# CV060_POWER.net
KiCad netlist of a schematic drawn in Altium Designer
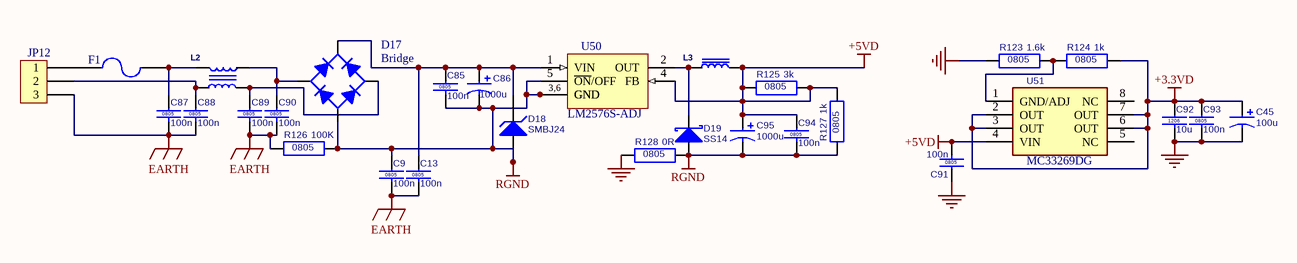
[diagram p0: CV060_POWER.SchDoc]

(export (version "E")
  (design (tool "Eeschema 10.0.6"))
  (components
    (comp (ref "C9")
      (value "100n")
      (footprint "RC0805")
      (description "Chip capacitor, 20p")
      (fields
        (field (name "VOLTAGE") "50V")
        (field (name "MANUFACTURER") "KEMET, YAGEO")
        (field (name "CASE") "0805")
        (field (name "PUBLISHER") "ppavlov")
      )
      (libsource (lib "Aldiva_Altium_Library") (part "Capacitor_nonpolar_case"))
    )
    (comp (ref "C13")
      (value "100n")
      (footprint "RC0805")
      (description "Chip capacitor, 20p")
      (fields
        (field (name "VOLTAGE") "50V")
        (field (name "MANUFACTURER") "KEMET, YAGEO")
        (field (name "CASE") "0805")
        (field (name "PUBLISHER") "ppavlov")
      )
      (libsource (lib "Aldiva_Altium_Library") (part "Capacitor_nonpolar_case"))
    )
    (comp (ref "C45")
      (value "100u")
      (footprint "CEH12.5D5P2.5")
      (description "Electrolytic capacitor")
      (fields
        (field (name "PART NUMBER") "CEH12.5D5P2.5M-16V-100U")
        (field (name "VOLTAGE") "16V")
        (field (name "PUBLISHER") "ppavlov")
      )
      (libsource (lib "Aldiva_Altium_Library") (part "Capacitor_polar"))
    )
    (comp (ref "C85")
      (value "100n")
      (footprint "RC0805")
      (description "Chip capacitor, 20p")
      (fields
        (field (name "VOLTAGE") "50V")
        (field (name "MANUFACTURER") "KEMET, YAGEO")
        (field (name "CASE") "0805")
        (field (name "PUBLISHER") "ppavlov")
      )
      (libsource (lib "Aldiva_Altium_Library") (part "Capacitor_nonpolar_case"))
    )
    (comp (ref "C86")
      (value "1000u")
      (footprint "CEH25D18P7.5")
      (description "Electrolytic capacitor")
      (fields
        (field (name "PART NUMBER") "CEH25D12.5P5.0M-50V-1000U")
        (field (name "VOLTAGE") "50V")
        (field (name "PUBLISHER") "ppavlov")
      )
      (libsource (lib "Aldiva_Altium_Library") (part "Capacitor_polar"))
    )
    (comp (ref "C87")
      (value "100n")
      (footprint "RC0805")
      (description "Chip capacitor, 20p")
      (fields
        (field (name "VOLTAGE") "50V")
        (field (name "MANUFACTURER") "KEMET, YAGEO")
        (field (name "CASE") "0805")
        (field (name "PUBLISHER") "ppavlov")
      )
      (libsource (lib "Aldiva_Altium_Library") (part "Capacitor_nonpolar_case"))
    )
    (comp (ref "C88")
      (value "100n")
      (footprint "RC0805")
      (description "Chip capacitor, 20p")
      (fields
        (field (name "VOLTAGE") "50V")
        (field (name "MANUFACTURER") "KEMET, YAGEO")
        (field (name "CASE") "0805")
        (field (name "PUBLISHER") "ppavlov")
      )
      (libsource (lib "Aldiva_Altium_Library") (part "Capacitor_nonpolar_case"))
    )
    (comp (ref "C89")
      (value "100n")
      (footprint "RC0805")
      (description "Chip capacitor, 20p")
      (fields
        (field (name "VOLTAGE") "50V")
        (field (name "MANUFACTURER") "KEMET, YAGEO")
        (field (name "CASE") "0805")
        (field (name "PUBLISHER") "ppavlov")
      )
      (libsource (lib "Aldiva_Altium_Library") (part "Capacitor_nonpolar_case"))
    )
    (comp (ref "C90")
      (value "100n")
      (footprint "RC0805")
      (description "Chip capacitor, 20p")
      (fields
        (field (name "VOLTAGE") "50V")
        (field (name "MANUFACTURER") "KEMET, YAGEO")
        (field (name "CASE") "0805")
        (field (name "PUBLISHER") "ppavlov")
      )
      (libsource (lib "Aldiva_Altium_Library") (part "Capacitor_nonpolar_case"))
    )
    (comp (ref "C91")
      (value "100n")
      (footprint "RC0805")
      (description "Chip capacitor, 20p")
      (fields
        (field (name "VOLTAGE") "50V")
        (field (name "MANUFACTURER") "KEMET, YAGEO")
        (field (name "CASE") "0805")
        (field (name "PUBLISHER") "ppavlov")
      )
      (libsource (lib "Aldiva_Altium_Library") (part "Capacitor_nonpolar_case"))
    )
    (comp (ref "C92")
      (value "10u")
      (footprint "RC1206")
      (description "Chip capacitor, 20p")
      (fields
        (field (name "VOLTAGE") "10V")
        (field (name "MANUFACTURER") "AVX")
        (field (name "CASE") "1206")
        (field (name "PUBLISHER") "tkondratyuk")
      )
      (libsource (lib "Aldiva_Altium_Library") (part "Capacitor_nonpolar_case"))
    )
    (comp (ref "C93")
      (value "100n")
      (footprint "RC0805")
      (description "Chip capacitor, 20p")
      (fields
        (field (name "VOLTAGE") "50V")
        (field (name "MANUFACTURER") "KEMET, YAGEO")
        (field (name "CASE") "0805")
        (field (name "PUBLISHER") "ppavlov")
      )
      (libsource (lib "Aldiva_Altium_Library") (part "Capacitor_nonpolar_case"))
    )
    (comp (ref "C94")
      (value "100n")
      (footprint "RC0805")
      (description "Chip capacitor, 20p")
      (fields
        (field (name "VOLTAGE") "50V")
        (field (name "MANUFACTURER") "KEMET, YAGEO")
        (field (name "CASE") "0805")
        (field (name "PUBLISHER") "ppavlov")
      )
      (libsource (lib "Aldiva_Altium_Library") (part "Capacitor_nonpolar_case"))
    )
    (comp (ref "C95")
      (value "1000u")
      (footprint "CEH12.5D10P5.0")
      (description "Electrolytic capacitor")
      (fields
        (field (name "PART NUMBER") "CEH25D12.5P5.0M-35V-1000U")
        (field (name "VOLTAGE") "35V")
        (field (name "PUBLISHER") "ppavlov")
      )
      (libsource (lib "Aldiva_Altium_Library") (part "Capacitor_polar"))
    )
    (comp (ref "D17")
      (value "Bridge")
      (footprint "KBPM")
      (description "Bridge 2A 600V")
      (fields
        (field (name "PART NUMBER") "2KBP06M")
        (field (name "VOLTAGE") "600V")
        (field (name "PUBLISHER") "ppavlov")
      )
      (libsource (lib "Aldiva_Altium_Library") (part "Bridge"))
    )
    (comp (ref "D18")
      (value "Zenner_diode")
      (footprint "SMB")
      (description "Transient Voltage Suppressor")
      (fields
        (field (name "PART NUMBER") "SMBJ24")
        (field (name "VOLTAGE") "24V")
        (field (name "MANUFACTURER") "Fairchild")
        (field (name "PUBLISHER") "tkondratyuk")
      )
      (libsource (lib "Aldiva_Altium_Library") (part "Zenner_diode"))
    )
    (comp (ref "D19")
      (value "Schottky_diode")
      (footprint "SMA")
      (description "Surface Mount Schottky Barrier Rectifier")
      (fields
        (field (name "PART NUMBER") "SS14")
        (field (name "VOLTAGE") "40V")
        (field (name "MANUFACTURER") "Fairchild, Vishay")
        (field (name "PUBLISHER") "tkondratyuk")
      )
      (libsource (lib "Aldiva_Altium_Library") (part "Schottky_diode"))
    )
    (comp (ref "F1")
      (value "RXEF135")
      (footprint "POLYSW_RXEF135")
      (description "Polyswitch RXEF135 fuse")
      (fields
        (field (name "VOLTAGE") "72V")
        (field (name "MANUFACTURER") "Polyswitch")
        (field (name "PUBLISHER") "ppavlov")
      )
      (libsource (lib "Aldiva_Altium_Library") (part "RXEF135"))
    )
    (comp (ref "JP12")
      (value "Header 3pins")
      (footprint "PHENIX_5MM _3p3D")
      (description "5.08mm angled 3pins receptabe")
      (fields (field (name "PART NUMBER") "2EDGR-5.0-03P-14") (field (name "PUBLISHER") "ppavlov"))
      (libsource (lib "Aldiva_Altium_Library") (part "Header 3pins"))
    )
    (comp (ref "L2")
      (value "linear_filter1")
      (footprint "UU157-01")
      (description "Linear filter")
      (fields
        (field (name "PART NUMBER") "UU157-01")
        (field (name "TOLERANCE") "20%")
        (field (name "AUTHOR") "PPavlov")
        (field (name "PUBLISHER") "ppavlov")
      )
      (libsource (lib "Aldiva_Altium_Library") (part "linear_filter1"))
    )
    (comp (ref "L3")
      (value "INDUCTOR2")
      (footprint "IH12.5D10P5.0")
      (description "Through hole Power Inductor")
      (fields
        (field (name "PART NUMBER") "RB0914-151KLA")
        (field (name "TOLERANCE") "20%")
        (field (name "AUTHOR") "PPavlov")
        (field (name "PUBLISHER") "ppavlov")
      )
      (libsource (lib "Aldiva_Altium_Library") (part "INDUCTOR2"))
    )
    (comp (ref "R123")
      (value "1.6k")
      (footprint "RC0805")
      (description "Chip resistor")
      (fields
        (field (name "CASE") "0805")
        (field (name "PART NUMBER") "RC0805F-1K60")
        (field (name "VOLTAGE") "200V")
        (field (name "PUBLISHER") "ppavlov")
      )
      (libsource (lib "Aldiva_Altium_Library") (part "Resistor"))
    )
    (comp (ref "R124")
      (value "1k")
      (footprint "RC0805")
      (description "Chip resistor")
      (fields
        (field (name "CASE") "0805")
        (field (name "PART NUMBER") "RC0805F-1K00")
        (field (name "VOLTAGE") "200V")
        (field (name "PUBLISHER") "ppavlov")
      )
      (libsource (lib "Aldiva_Altium_Library") (part "Resistor"))
    )
    (comp (ref "R125")
      (value "3k")
      (footprint "RC0805")
      (description "Chip resistor")
      (fields
        (field (name "CASE") "0805")
        (field (name "PART NUMBER") "RC0805F-3K00")
        (field (name "VOLTAGE") "200V")
        (field (name "PUBLISHER") "ppavlov")
      )
      (libsource (lib "Aldiva_Altium_Library") (part "Resistor"))
    )
    (comp (ref "R126")
      (value "100K")
      (footprint "RC0805")
      (description "Chip resistor")
      (fields
        (field (name "CASE") "0805")
        (field (name "PART NUMBER") "RC0805F-100K")
        (field (name "VOLTAGE") "200V")
        (field (name "PUBLISHER") "ppavlov")
      )
      (libsource (lib "Aldiva_Altium_Library") (part "Resistor"))
    )
    (comp (ref "R127")
      (value "1k")
      (footprint "RC0805")
      (description "Chip resistor")
      (fields
        (field (name "CASE") "0805")
        (field (name "PART NUMBER") "RC0805F-1K00")
        (field (name "VOLTAGE") "200V")
        (field (name "PUBLISHER") "ppavlov")
      )
      (libsource (lib "Aldiva_Altium_Library") (part "Resistor"))
    )
    (comp (ref "R128")
      (value "0R")
      (footprint "RC0805")
      (description "Chip resistor")
      (fields
        (field (name "CASE") "0805")
        (field (name "PART NUMBER") "RC0805F-000R")
        (field (name "VOLTAGE") "200V")
        (field (name "PUBLISHER") "ppavlov")
      )
      (libsource (lib "Aldiva_Altium_Library") (part "Resistor"))
    )
    (comp (ref "U50")
      (value "LM2576S-ADJ")
      (footprint "TO-263")
      (description "3A Step-Down Voltage Regulator")
      (fields (field (name "MANUFACTURER") "National semiconductor") (field (name "PUBLISHER") "ppavlov"))
      (libsource (lib "Aldiva_Altium_Library") (part "LM2576S-ADJ"))
    )
    (comp (ref "U51")
      (value "MC33269DG")
      (footprint "SO-8")
      (description "LDO 800ma ADJ")
      (fields
        (field (name "PART NUMBER") "MC33269DG")
        (field (name "MANUFACTURER") "ON Semiconductor")
        (field (name "PUBLISHER") "ppavlov")
      )
      (libsource (lib "Aldiva_Altium_Library") (part "MC33269D"))
    )
  )
  (nets
    (net (code "1") (name "+3.3VD") (class "Default")
      (node (ref "C45") (pin "1") (pinfunction "1_1") (pintype "passive"))
      (node (ref "C92") (pin "1") (pinfunction "1_1") (pintype "passive"))
      (node (ref "C93") (pin "1") (pinfunction "1_1") (pintype "passive"))
      (node (ref "R124") (pin "2") (pinfunction "2_2") (pintype "passive"))
      (node (ref "U51") (pin "2") (pinfunction "OUT_2") (pintype "passive"))
      (node (ref "U51") (pin "3") (pinfunction "OUT_3") (pintype "passive"))
      (node (ref "U51") (pin "6") (pinfunction "OUT_6") (pintype "passive"))
      (node (ref "U51") (pin "7") (pinfunction "OUT_7") (pintype "passive"))
    )
    (net (code "2") (name "+5VD") (class "Default")
      (node (ref "C91") (pin "2") (pinfunction "2_2") (pintype "passive"))
      (node (ref "C94") (pin "1") (pinfunction "1_1") (pintype "passive"))
      (node (ref "C95") (pin "1") (pinfunction "1_1") (pintype "passive"))
      (node (ref "L3") (pin "2") (pinfunction "2_2") (pintype "passive"))
      (node (ref "R125") (pin "1") (pinfunction "1_1") (pintype "passive"))
      (node (ref "R125") (pin "2") (pinfunction "2_2") (pintype "passive"))
      (node (ref "R127") (pin "2") (pinfunction "2_2") (pintype "passive"))
      (node (ref "U50") (pin "4") (pinfunction "FB_4") (pintype "input"))
      (node (ref "U51") (pin "4") (pinfunction "VIN_4") (pintype "passive"))
    )
    (net (code "3") (name "DGND") (class "Default")
      (node (ref "C45") (pin "2") (pinfunction "2_2") (pintype "passive"))
      (node (ref "C91") (pin "1") (pinfunction "1_1") (pintype "passive"))
      (node (ref "C92") (pin "2") (pinfunction "2_2") (pintype "passive"))
      (node (ref "C93") (pin "2") (pinfunction "2_2") (pintype "passive"))
      (node (ref "R123") (pin "1") (pinfunction "1_1") (pintype "passive"))
      (node (ref "R128") (pin "1") (pinfunction "1_1") (pintype "passive"))
    )
    (net (code "4") (name "EARTH") (class "Default")
      (node (ref "C13") (pin "2") (pinfunction "2_2") (pintype "passive"))
      (node (ref "C87") (pin "2") (pinfunction "2_2") (pintype "passive"))
      (node (ref "C88") (pin "2") (pinfunction "2_2") (pintype "passive"))
      (node (ref "C89") (pin "2") (pinfunction "2_2") (pintype "passive"))
      (node (ref "C9") (pin "2") (pinfunction "2_2") (pintype "passive"))
      (node (ref "C90") (pin "2") (pinfunction "2_2") (pintype "passive"))
      (node (ref "JP12") (pin "3") (pinfunction "3_3") (pintype "passive"))
      (node (ref "R126") (pin "1") (pinfunction "1_1") (pintype "passive"))
    )
    (net (code "5") (name "Net-(C87-Pad1)") (class "Default")
      (node (ref "C87") (pin "1") (pinfunction "1_1") (pintype "passive"))
      (node (ref "F1") (pin "2") (pinfunction "2_2") (pintype "passive"))
      (node (ref "L2") (pin "1") (pinfunction "1_1") (pintype "passive"))
    )
    (net (code "6") (name "Net-(C88-Pad1)") (class "Default")
      (node (ref "C88") (pin "1") (pinfunction "1_1") (pintype "passive"))
      (node (ref "JP12") (pin "2") (pinfunction "2_2") (pintype "passive"))
      (node (ref "L2") (pin "3") (pinfunction "3_3") (pintype "passive"))
    )
    (net (code "7") (name "Net-(C89-Pad1)") (class "Default")
      (node (ref "C89") (pin "1") (pinfunction "1_1") (pintype "passive"))
      (node (ref "D17") (pin "2") (pinfunction "C_2") (pintype "passive"))
      (node (ref "L2") (pin "4") (pinfunction "4_4") (pintype "passive"))
    )
    (net (code "8") (name "Net-(C90-Pad1)") (class "Default")
      (node (ref "C90") (pin "1") (pinfunction "1_1") (pintype "passive"))
      (node (ref "D17") (pin "4") (pinfunction "C_4") (pintype "passive"))
      (node (ref "L2") (pin "2") (pinfunction "2_2") (pintype "passive"))
    )
    (net (code "9") (name "Net-(D17-K)") (class "Default")
      (node (ref "C13") (pin "1") (pinfunction "1_1") (pintype "passive"))
      (node (ref "C85") (pin "1") (pinfunction "1_1") (pintype "passive"))
      (node (ref "C86") (pin "1") (pinfunction "1_1") (pintype "passive"))
      (node (ref "D17") (pin "1") (pinfunction "K_1") (pintype "passive"))
      (node (ref "D18") (pin "1") (pinfunction "K_1") (pintype "passive"))
      (node (ref "U50") (pin "1") (pinfunction "VIN_1") (pintype "input"))
    )
    (net (code "10") (name "Net-(D19-K)") (class "Default")
      (node (ref "D19") (pin "1") (pinfunction "K_1") (pintype "passive"))
      (node (ref "L3") (pin "1") (pinfunction "1_1") (pintype "passive"))
      (node (ref "U50") (pin "2") (pinfunction "OUT_2") (pintype "open_emitter"))
    )
    (net (code "11") (name "Net-(F1-Pad1)") (class "Default")
      (node (ref "F1") (pin "1") (pinfunction "1_1") (pintype "passive"))
      (node (ref "JP12") (pin "1") (pinfunction "1_1") (pintype "passive"))
    )
    (net (code "12") (name "Net-(U51-GND{slash}ADJ)") (class "Default")
      (node (ref "R123") (pin "2") (pinfunction "2_2") (pintype "passive"))
      (node (ref "R124") (pin "1") (pinfunction "1_1") (pintype "passive"))
      (node (ref "U51") (pin "1") (pinfunction "GND/ADJ_1") (pintype "passive"))
    )
    (net (code "13") (name "RGND") (class "Default")
      (node (ref "C85") (pin "2") (pinfunction "2_2") (pintype "passive"))
      (node (ref "C86") (pin "2") (pinfunction "2_2") (pintype "passive"))
      (node (ref "C9") (pin "1") (pinfunction "1_1") (pintype "passive"))
      (node (ref "C94") (pin "2") (pinfunction "2_2") (pintype "passive"))
      (node (ref "C95") (pin "2") (pinfunction "2_2") (pintype "passive"))
      (node (ref "D17") (pin "3") (pinfunction "A_3") (pintype "passive"))
      (node (ref "D18") (pin "2") (pinfunction "A_2") (pintype "passive"))
      (node (ref "D19") (pin "2") (pinfunction "A_2") (pintype "passive"))
      (node (ref "R126") (pin "2") (pinfunction "2_2") (pintype "passive"))
      (node (ref "R127") (pin "1") (pinfunction "1_1") (pintype "passive"))
      (node (ref "R128") (pin "2") (pinfunction "2_2") (pintype "passive"))
      (node (ref "U50") (pin "3") (pinfunction "GND_3") (pintype "power_in"))
      (node (ref "U50") (pin "5") (pinfunction "~{ON}/OFF_5") (pintype "passive"))
      (node (ref "U50") (pin "6") (pinfunction "GND_6") (pintype "power_in"))
    )
    (net (code "14") (name "unconnected-(U51-NC-Pad5)") (class "Default")
      (node (ref "U51") (pin "5") (pinfunction "NC_5") (pintype "passive"))
    )
    (net (code "15") (name "unconnected-(U51-NC-Pad8)") (class "Default")
      (node (ref "U51") (pin "8") (pinfunction "NC_8") (pintype "passive"))
    )
  )
)
